# CPU.net
KiCad netlist of a schematic drawn in Altium Designer
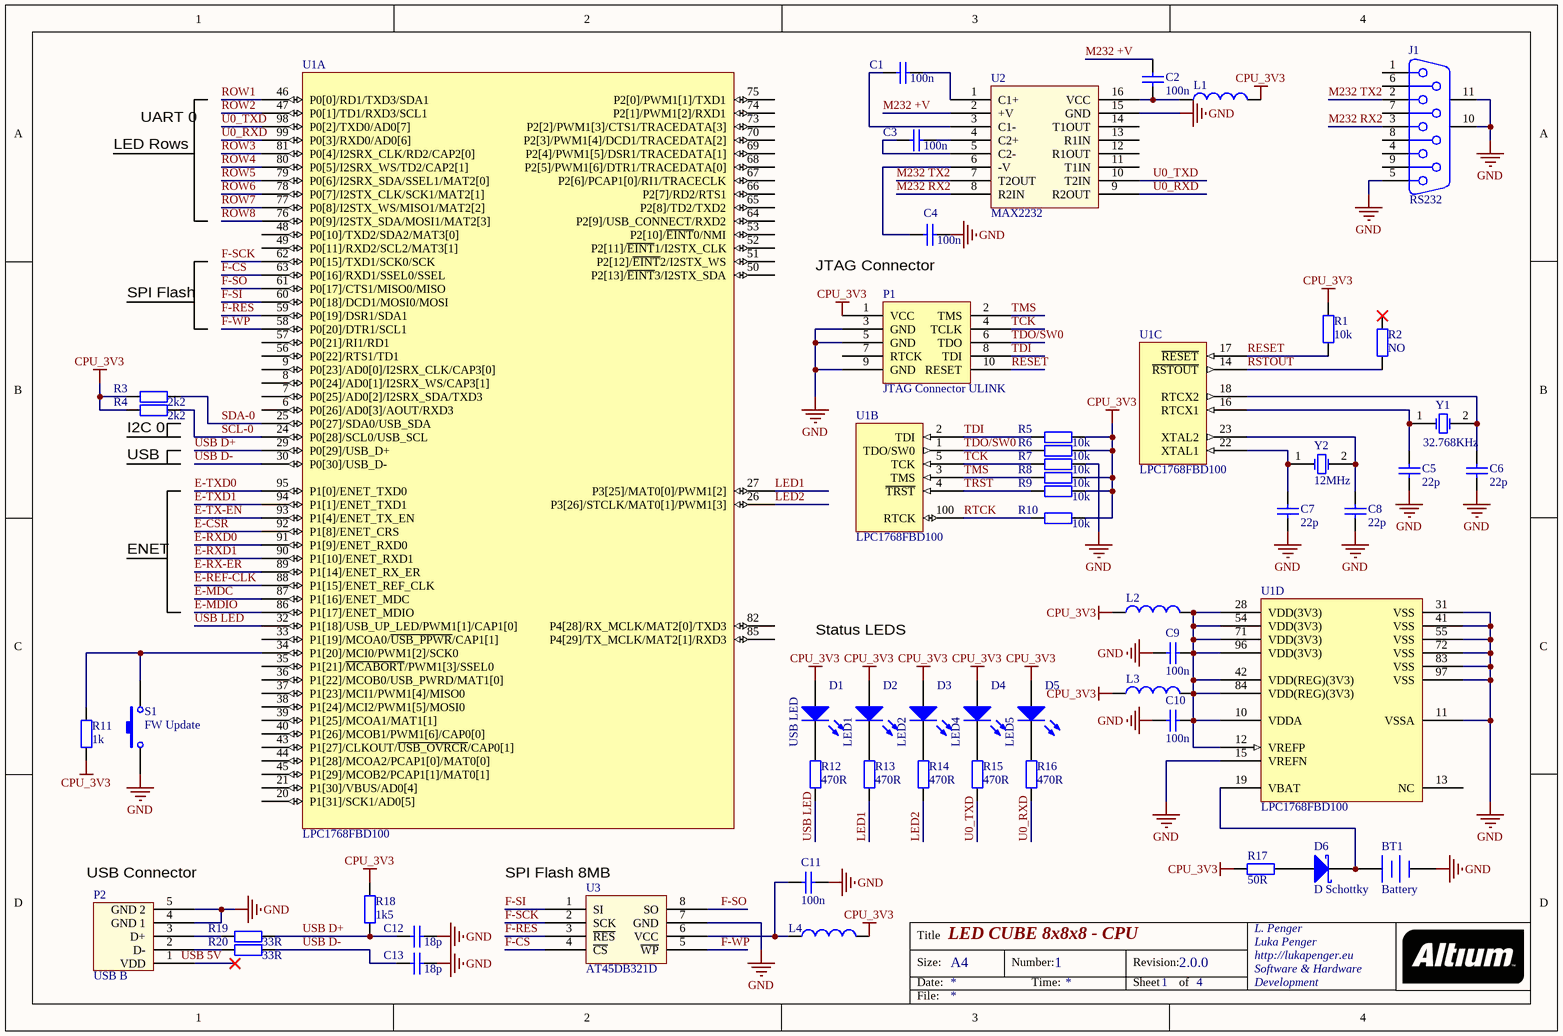
[diagram p0: CPU.SchDoc]

(export (version "E")
  (design (tool "Eeschema 10.0.6"))
  (components
    (comp (ref "BT1")
      (value "Battery")
      (footprint "Battery capacitor")
      (description "Multicell Battery")
      (fields (field (name "PUBLISHER") "Altium Limited"))
      (libsource (lib "Miscellaneous Devices") (part "Battery"))
    )
    (comp (ref "C1")
      (value "100n")
      (footprint "1608[0603]")
      (description "Capacitor")
      (fields (field (name "PUBLISHER") "Altium Limited"))
      (libsource (lib "Miscellaneous Devices") (part "Cap"))
    )
    (comp (ref "C2")
      (value "100n")
      (footprint "1608[0603]")
      (description "Capacitor")
      (fields (field (name "PUBLISHER") "Altium Limited"))
      (libsource (lib "Miscellaneous Devices") (part "Cap"))
    )
    (comp (ref "C3")
      (value "100n")
      (footprint "1608[0603]")
      (description "Capacitor")
      (fields (field (name "PUBLISHER") "Altium Limited"))
      (libsource (lib "Miscellaneous Devices") (part "Cap"))
    )
    (comp (ref "C4")
      (value "100n")
      (footprint "1608[0603]")
      (description "Capacitor")
      (fields (field (name "PUBLISHER") "Altium Limited"))
      (libsource (lib "Miscellaneous Devices") (part "Cap"))
    )
    (comp (ref "C5")
      (value "22p")
      (footprint "1608[0603]")
      (description "Capacitor")
      (fields (field (name "PUBLISHER") "Altium Limited"))
      (libsource (lib "Miscellaneous Devices") (part "Cap"))
    )
    (comp (ref "C6")
      (value "22p")
      (footprint "1608[0603]")
      (description "Capacitor")
      (fields (field (name "PUBLISHER") "Altium Limited"))
      (libsource (lib "Miscellaneous Devices") (part "Cap"))
    )
    (comp (ref "C7")
      (value "22p")
      (footprint "1608[0603]")
      (description "Capacitor")
      (fields (field (name "PUBLISHER") "Altium Limited"))
      (libsource (lib "Miscellaneous Devices") (part "Cap"))
    )
    (comp (ref "C8")
      (value "22p")
      (footprint "1608[0603]")
      (description "Capacitor")
      (fields (field (name "PUBLISHER") "Altium Limited"))
      (libsource (lib "Miscellaneous Devices") (part "Cap"))
    )
    (comp (ref "C9")
      (value "100n")
      (footprint "1608[0603]")
      (description "Capacitor")
      (fields (field (name "PUBLISHER") "Altium Limited"))
      (libsource (lib "Miscellaneous Devices") (part "Cap"))
    )
    (comp (ref "C10")
      (value "100n")
      (footprint "1608[0603]")
      (description "Capacitor")
      (fields (field (name "PUBLISHER") "Altium Limited"))
      (libsource (lib "Miscellaneous Devices") (part "Cap"))
    )
    (comp (ref "C11")
      (value "100n")
      (footprint "1608[0603]")
      (description "Capacitor")
      (fields (field (name "PUBLISHER") "Altium Limited"))
      (libsource (lib "Miscellaneous Devices") (part "Cap"))
    )
    (comp (ref "C12")
      (value "18p")
      (footprint "1608[0603]")
      (description "Capacitor")
      (fields (field (name "PUBLISHER") "Altium Limited"))
      (libsource (lib "Miscellaneous Devices") (part "Cap"))
    )
    (comp (ref "C13")
      (value "18p")
      (footprint "1608[0603]")
      (description "Capacitor")
      (fields (field (name "PUBLISHER") "Altium Limited"))
      (libsource (lib "Miscellaneous Devices") (part "Cap"))
    )
    (comp (ref "D1")
      (value "USB LED")
      (footprint "LED-1")
      (description "Typical INFRARED GaAs LED")
      (fields (field (name "PUBLISHER") "Altium Limited"))
      (libsource (lib "Miscellaneous Devices") (part "LED0"))
    )
    (comp (ref "D2")
      (value "LED1")
      (footprint "LED-1")
      (description "Typical INFRARED GaAs LED")
      (fields (field (name "PUBLISHER") "Altium Limited"))
      (libsource (lib "Miscellaneous Devices") (part "LED0"))
    )
    (comp (ref "D3")
      (value "LED2")
      (footprint "LED-1")
      (description "Typical INFRARED GaAs LED")
      (fields (field (name "PUBLISHER") "Altium Limited"))
      (libsource (lib "Miscellaneous Devices") (part "LED0"))
    )
    (comp (ref "D4")
      (value "LED4")
      (footprint "LED-1")
      (description "Typical INFRARED GaAs LED")
      (fields (field (name "PUBLISHER") "Altium Limited"))
      (libsource (lib "Miscellaneous Devices") (part "LED0"))
    )
    (comp (ref "D5")
      (value "LED5")
      (footprint "LED-1")
      (description "Typical INFRARED GaAs LED")
      (fields (field (name "PUBLISHER") "Altium Limited"))
      (libsource (lib "Miscellaneous Devices") (part "LED0"))
    )
    (comp (ref "D6")
      (value "D Schottky")
      (footprint "SMB")
      (description "Schottky Diode")
      (fields (field (name "PUBLISHER") "Altium Limited"))
      (libsource (lib "Miscellaneous Devices") (part "D Schottky"))
    )
    (comp (ref "J1")
      (value "RS232")
      (footprint "DSUB1.385-2H9")
      (description "Receptacle Assembly, 9 Position, Right Angle")
      (fields (field (name "PUBLISHER") "Altium Limited"))
      (libsource (lib "Miscellaneous Connectors") (part "D Connector 9"))
    )
    (comp (ref "L1")
      (value "Inductor")
      (footprint "1608[0603]")
      (fields (field (name "PUBLISHER") "Altium Limited"))
      (libsource (lib "Miscellaneous Devices") (part "Inductor"))
    )
    (comp (ref "L2")
      (value "Inductor")
      (footprint "1608[0603]")
      (fields (field (name "PUBLISHER") "Altium Limited"))
      (libsource (lib "Miscellaneous Devices") (part "Inductor"))
    )
    (comp (ref "L3")
      (value "Inductor")
      (footprint "1608[0603]")
      (fields (field (name "PUBLISHER") "Altium Limited"))
      (libsource (lib "Miscellaneous Devices") (part "Inductor"))
    )
    (comp (ref "L4")
      (value "Inductor")
      (footprint "1608[0603]")
      (fields (field (name "PUBLISHER") "Altium Limited"))
      (libsource (lib "Miscellaneous Devices") (part "Inductor"))
    )
    (comp (ref "P1")
      (value "JTAG Connector ULINK")
      (footprint "JTAG Connector ULINK")
      (description "JTAG Connector")
      (libsource (lib "LP_Lib") (part "JTAG Connector ULINK"))
    )
    (comp (ref "P2")
      (value "USB B")
      (footprint "USB B")
      (description "USB Connector")
      (libsource (lib "LP_Lib") (part "USB B"))
    )
    (comp (ref "R1")
      (value "10k")
      (footprint "1608[0603]")
      (description "Resistor")
      (fields (field (name "PUBLISHER") "Altium Limited"))
      (libsource (lib "") (part "Res2_1"))
    )
    (comp (ref "R2")
      (value "NO")
      (footprint "1608[0603]")
      (description "Resistor")
      (fields (field (name "PUBLISHER") "Altium Limited"))
      (libsource (lib "") (part "Res2_1"))
    )
    (comp (ref "R3")
      (value "2k2")
      (footprint "1608[0603]")
      (description "Resistor")
      (fields (field (name "PUBLISHER") "Altium Limited"))
      (libsource (lib "") (part "Res2_2"))
    )
    (comp (ref "R4")
      (value "2k2")
      (footprint "1608[0603]")
      (description "Resistor")
      (fields (field (name "PUBLISHER") "Altium Limited"))
      (libsource (lib "") (part "Res2_2"))
    )
    (comp (ref "R5")
      (value "10k")
      (footprint "1608[0603]")
      (description "Resistor")
      (fields (field (name "PUBLISHER") "Altium Limited"))
      (libsource (lib "") (part "Res2_2"))
    )
    (comp (ref "R6")
      (value "10k")
      (footprint "1608[0603]")
      (description "Resistor")
      (fields (field (name "PUBLISHER") "Altium Limited"))
      (libsource (lib "") (part "Res2_2"))
    )
    (comp (ref "R7")
      (value "10k")
      (footprint "1608[0603]")
      (description "Resistor")
      (fields (field (name "PUBLISHER") "Altium Limited"))
      (libsource (lib "") (part "Res2_2"))
    )
    (comp (ref "R8")
      (value "10k")
      (footprint "1608[0603]")
      (description "Resistor")
      (fields (field (name "PUBLISHER") "Altium Limited"))
      (libsource (lib "") (part "Res2_2"))
    )
    (comp (ref "R9")
      (value "10k")
      (footprint "1608[0603]")
      (description "Resistor")
      (fields (field (name "PUBLISHER") "Altium Limited"))
      (libsource (lib "") (part "Res2_2"))
    )
    (comp (ref "R10")
      (value "10k")
      (footprint "1608[0603]")
      (description "Resistor")
      (fields (field (name "PUBLISHER") "Altium Limited"))
      (libsource (lib "") (part "Res2_2"))
    )
    (comp (ref "R11")
      (value "1k")
      (footprint "1608[0603]")
      (description "Resistor")
      (fields (field (name "PUBLISHER") "Altium Limited"))
      (libsource (lib "") (part "Res2_1"))
    )
    (comp (ref "R12")
      (value "470R")
      (footprint "1608[0603]")
      (description "Resistor")
      (fields (field (name "PUBLISHER") "Altium Limited"))
      (libsource (lib "") (part "Res2_1"))
    )
    (comp (ref "R13")
      (value "470R")
      (footprint "1608[0603]")
      (description "Resistor")
      (fields (field (name "PUBLISHER") "Altium Limited"))
      (libsource (lib "") (part "Res2_1"))
    )
    (comp (ref "R14")
      (value "470R")
      (footprint "1608[0603]")
      (description "Resistor")
      (fields (field (name "PUBLISHER") "Altium Limited"))
      (libsource (lib "") (part "Res2_1"))
    )
    (comp (ref "R15")
      (value "470R")
      (footprint "1608[0603]")
      (description "Resistor")
      (fields (field (name "PUBLISHER") "Altium Limited"))
      (libsource (lib "") (part "Res2_1"))
    )
    (comp (ref "R16")
      (value "470R")
      (footprint "1608[0603]")
      (description "Resistor")
      (fields (field (name "PUBLISHER") "Altium Limited"))
      (libsource (lib "") (part "Res2_1"))
    )
    (comp (ref "R17")
      (value "50R")
      (footprint "6-0805_N")
      (description "Resistor")
      (fields (field (name "PUBLISHER") "Altium Limited"))
      (libsource (lib "") (part "Res2_3"))
    )
    (comp (ref "R18")
      (value "1k5")
      (footprint "1608[0603]")
      (description "Resistor")
      (fields (field (name "PUBLISHER") "Altium Limited"))
      (libsource (lib "Miscellaneous Devices") (part "Res2"))
    )
    (comp (ref "R19")
      (value "33R")
      (footprint "1608[0603]")
      (description "Resistor")
      (fields (field (name "PUBLISHER") "Altium Limited"))
      (libsource (lib "") (part "Res2_3"))
    )
    (comp (ref "R20")
      (value "33R")
      (footprint "1608[0603]")
      (description "Resistor")
      (fields (field (name "PUBLISHER") "Altium Limited"))
      (libsource (lib "") (part "Res2_3"))
    )
    (comp (ref "S1")
      (value "FW Update")
      (footprint "SWITCH-TACTILE-90")
      (description "Switch")
      (fields (field (name "PUBLISHER") "Altium Limited"))
      (libsource (lib "Miscellaneous Devices") (part "SW-PB"))
    )
    (comp (ref "U1")
      (value "LPC1768FBD100")
      (footprint "SOT407-1_N")
      (fields (field (name "PUBLISHER") "Altium Limited"))
      (libsource (lib "LukaLIBRARY") (part "LPC1768FBD100"))
    )
    (comp (ref "U2")
      (value "MAX2232")
      (footprint "SOIC16_N")
      (description "Dual 232 +3V3")
      (libsource (lib "LP_Lib") (part "MAX2232"))
    )
    (comp (ref "U3")
      (value "AT45DB321D")
      (footprint "AT45DB321D")
      (description "SPI Flash 32MB")
      (libsource (lib "LP_Lib") (part "AT45DB321D"))
    )
    (comp (ref "Y1")
      (value "32.768KHz")
      (footprint "Crystal 4.1x1.5")
      (description "Crystal Oscillator")
      (fields (field (name "PUBLISHER") "Altium Limited"))
      (libsource (lib "Miscellaneous Devices") (part "XTAL"))
    )
    (comp (ref "Y2")
      (value "12MHz")
      (footprint "5x3.2 Crystal")
      (description "Crystal Oscillator")
      (fields (field (name "PUBLISHER") "Altium Limited"))
      (libsource (lib "Miscellaneous Devices") (part "XTAL"))
    )
  )
  (nets
    (net (code "1") (name "/E-CSR") (class "Default")
      (node (ref "U1") (pin "92") (pinfunction "P1[8]/ENET_CRS_92") (pintype "bidirectional"))
    )
    (net (code "2") (name "/E-MDC") (class "Default")
      (node (ref "U1") (pin "87") (pinfunction "P1[16]/ENET_MDC_87") (pintype "bidirectional"))
    )
    (net (code "3") (name "/E-MDIO") (class "Default")
      (node (ref "U1") (pin "86") (pinfunction "P1[17]/ENET_MDIO_86") (pintype "bidirectional"))
    )
    (net (code "4") (name "/E-REF-CLK") (class "Default")
      (node (ref "U1") (pin "88") (pinfunction "P1[15]/ENET_REF_CLK_88") (pintype "bidirectional"))
    )
    (net (code "5") (name "/E-RX-ER") (class "Default")
      (node (ref "U1") (pin "89") (pinfunction "P1[14]/ENET_RX_ER_89") (pintype "bidirectional"))
    )
    (net (code "6") (name "/E-RXD0") (class "Default")
      (node (ref "U1") (pin "91") (pinfunction "P1[9]/ENET_RXD0_91") (pintype "bidirectional"))
    )
    (net (code "7") (name "/E-RXD1") (class "Default")
      (node (ref "U1") (pin "90") (pinfunction "P1[10]/ENET_RXD1_90") (pintype "bidirectional"))
    )
    (net (code "8") (name "/E-TX-EN") (class "Default")
      (node (ref "U1") (pin "93") (pinfunction "P1[4]/ENET_TX_EN_93") (pintype "bidirectional"))
    )
    (net (code "9") (name "/E-TXD0") (class "Default")
      (node (ref "U1") (pin "95") (pinfunction "P1[0]/ENET_TXD0_95") (pintype "bidirectional"))
    )
    (net (code "10") (name "/E-TXD1") (class "Default")
      (node (ref "U1") (pin "94") (pinfunction "P1[1]/ENET_TXD1_94") (pintype "bidirectional"))
    )
    (net (code "11") (name "/F-CS") (class "Default")
      (node (ref "U1") (pin "63") (pinfunction "P0[16]/RXD1/SSEL0/SSEL_63") (pintype "bidirectional"))
      (node (ref "U3") (pin "4") (pinfunction "~{CS}_4") (pintype "passive"))
    )
    (net (code "12") (name "/F-RES") (class "Default")
      (node (ref "U1") (pin "59") (pinfunction "P0[19]/DSR1/SDA1_59") (pintype "bidirectional"))
      (node (ref "U3") (pin "3") (pinfunction "~{RES}_3") (pintype "passive"))
    )
    (net (code "13") (name "/F-SCK") (class "Default")
      (node (ref "U1") (pin "62") (pinfunction "P0[15]/TXD1/SCK0/SCK_62") (pintype "bidirectional"))
      (node (ref "U3") (pin "2") (pinfunction "SCK_2") (pintype "passive"))
    )
    (net (code "14") (name "/F-SI") (class "Default")
      (node (ref "U1") (pin "60") (pinfunction "P0[18]/DCD1/MOSI0/MOSI_60") (pintype "bidirectional"))
      (node (ref "U3") (pin "1") (pinfunction "SI_1") (pintype "passive"))
    )
    (net (code "15") (name "/F-SO") (class "Default")
      (node (ref "U1") (pin "61") (pinfunction "P0[17]/CTS1/MISO0/MISO_61") (pintype "bidirectional"))
      (node (ref "U3") (pin "8") (pinfunction "SO_8") (pintype "passive"))
    )
    (net (code "16") (name "/F-WP") (class "Default")
      (node (ref "U1") (pin "58") (pinfunction "P0[20]/DTR1/SCL1_58") (pintype "bidirectional"))
      (node (ref "U3") (pin "5") (pinfunction "~{WP}_5") (pintype "passive"))
    )
    (net (code "17") (name "/LED1") (class "Default")
      (node (ref "R13") (pin "1") (pinfunction "1_1") (pintype "passive"))
      (node (ref "U1") (pin "27") (pinfunction "P3[25]/MAT0[0]/PWM1[2]_27") (pintype "bidirectional"))
    )
    (net (code "18") (name "/LED2") (class "Default")
      (node (ref "R14") (pin "1") (pinfunction "1_1") (pintype "passive"))
      (node (ref "U1") (pin "26") (pinfunction "P3[26]/STCLK/MAT0[1]/PWM1[3]_26") (pintype "bidirectional"))
    )
    (net (code "19") (name "/M232 +V") (class "Default")
      (node (ref "C2") (pin "1") (pinfunction "1_1") (pintype "passive"))
      (node (ref "U2") (pin "2") (pinfunction "+V_2") (pintype "passive"))
    )
    (net (code "20") (name "/M232 RX2") (class "Default")
      (node (ref "J1") (pin "3") (pinfunction "3_3") (pintype "passive"))
      (node (ref "U2") (pin "8") (pinfunction "R2IN_8") (pintype "passive"))
    )
    (net (code "21") (name "/M232 TX2") (class "Default")
      (node (ref "J1") (pin "2") (pinfunction "2_2") (pintype "passive"))
      (node (ref "U2") (pin "7") (pinfunction "T2OUT_7") (pintype "passive"))
    )
    (net (code "22") (name "/RESET") (class "Default")
      (node (ref "P1") (pin "10") (pinfunction "RESET_10") (pintype "passive"))
      (node (ref "R1") (pin "1") (pinfunction "1_1") (pintype "passive"))
      (node (ref "U1") (pin "17") (pinfunction "~{RESET}_17") (pintype "input"))
    )
    (net (code "23") (name "/ROW1") (class "Default")
      (node (ref "U1") (pin "46") (pinfunction "P0[0]/RD1/TXD3/SDA1_46") (pintype "bidirectional"))
    )
    (net (code "24") (name "/ROW2") (class "Default")
      (node (ref "U1") (pin "47") (pinfunction "P0[1]/TD1/RXD3/SCL1_47") (pintype "bidirectional"))
    )
    (net (code "25") (name "/ROW3") (class "Default")
      (node (ref "U1") (pin "81") (pinfunction "P0[4]/I2SRX_CLK/RD2/CAP2[0]_81") (pintype "bidirectional"))
    )
    (net (code "26") (name "/ROW4") (class "Default")
      (node (ref "U1") (pin "80") (pinfunction "P0[5]/I2SRX_WS/TD2/CAP2[1]_80") (pintype "bidirectional"))
    )
    (net (code "27") (name "/ROW5") (class "Default")
      (node (ref "U1") (pin "79") (pinfunction "P0[6]/I2SRX_SDA/SSEL1/MAT2[0]_79") (pintype "bidirectional"))
    )
    (net (code "28") (name "/ROW6") (class "Default")
      (node (ref "U1") (pin "78") (pinfunction "P0[7]/I2STX_CLK/SCK1/MAT2[1]_78") (pintype "bidirectional"))
    )
    (net (code "29") (name "/ROW7") (class "Default")
      (node (ref "U1") (pin "77") (pinfunction "P0[8]/I2STX_WS/MISO1/MAT2[2]_77") (pintype "bidirectional"))
    )
    (net (code "30") (name "/ROW8") (class "Default")
      (node (ref "U1") (pin "76") (pinfunction "P0[9]/I2STX_SDA/MOSI1/MAT2[3]_76") (pintype "bidirectional"))
    )
    (net (code "31") (name "/RSTOUT") (class "Default")
      (node (ref "R2") (pin "1") (pinfunction "1_1") (pintype "passive"))
      (node (ref "U1") (pin "14") (pinfunction "~{RSTOUT}_14") (pintype "output"))
    )
    (net (code "32") (name "/RTCK") (class "Default")
      (node (ref "R10") (pin "1") (pinfunction "1_1") (pintype "passive"))
      (node (ref "U1") (pin "100") (pinfunction "RTCK_100") (pintype "bidirectional"))
    )
    (net (code "33") (name "/SCL-0") (class "Default")
      (node (ref "R4") (pin "2") (pinfunction "2_2") (pintype "passive"))
      (node (ref "U1") (pin "24") (pinfunction "P0[28]/SCL0/USB_SCL_24") (pintype "bidirectional"))
    )
    (net (code "34") (name "/SDA-0") (class "Default")
      (node (ref "R3") (pin "2") (pinfunction "2_2") (pintype "passive"))
      (node (ref "U1") (pin "25") (pinfunction "P0[27]/SDA0/USB_SDA_25") (pintype "bidirectional"))
    )
    (net (code "35") (name "/TCK") (class "Default")
      (node (ref "P1") (pin "4") (pinfunction "TCLK_4") (pintype "passive"))
      (node (ref "R7") (pin "1") (pinfunction "1_1") (pintype "passive"))
      (node (ref "U1") (pin "5") (pinfunction "TCK_5") (pintype "input"))
    )
    (net (code "36") (name "/TDI") (class "Default")
      (node (ref "P1") (pin "8") (pinfunction "TDI_8") (pintype "passive"))
      (node (ref "R5") (pin "1") (pinfunction "1_1") (pintype "passive"))
      (node (ref "U1") (pin "2") (pinfunction "TDI_2") (pintype "input"))
    )
    (net (code "37") (name "/TDO{slash}SW0") (class "Default")
      (node (ref "P1") (pin "6") (pinfunction "TDO_6") (pintype "passive"))
      (node (ref "R6") (pin "1") (pinfunction "1_1") (pintype "passive"))
      (node (ref "U1") (pin "1") (pinfunction "TDO/SW0_1") (pintype "output"))
    )
    (net (code "38") (name "/TMS") (class "Default")
      (node (ref "P1") (pin "2") (pinfunction "TMS_2") (pintype "passive"))
      (node (ref "R8") (pin "1") (pinfunction "1_1") (pintype "passive"))
      (node (ref "U1") (pin "3") (pinfunction "TMS_3") (pintype "input"))
    )
    (net (code "39") (name "/TRST") (class "Default")
      (node (ref "R9") (pin "1") (pinfunction "1_1") (pintype "passive"))
      (node (ref "U1") (pin "4") (pinfunction "~{TRST}_4") (pintype "input"))
    )
    (net (code "40") (name "/U0_RXD") (class "Default")
      (node (ref "R16") (pin "1") (pinfunction "1_1") (pintype "passive"))
      (node (ref "U1") (pin "99") (pinfunction "P0[3]/RXD0/AD0[6]_99") (pintype "bidirectional"))
      (node (ref "U2") (pin "9") (pinfunction "R2OUT_9") (pintype "passive"))
    )
    (net (code "41") (name "/U0_TXD") (class "Default")
      (node (ref "R15") (pin "1") (pinfunction "1_1") (pintype "passive"))
      (node (ref "U1") (pin "98") (pinfunction "P0[2]/TXD0/AD0[7]_98") (pintype "bidirectional"))
      (node (ref "U2") (pin "10") (pinfunction "T2IN_10") (pintype "passive"))
    )
    (net (code "43") (name "/USB D+") (class "Default")
      (node (ref "C12") (pin "1") (pinfunction "1_1") (pintype "passive"))
      (node (ref "R18") (pin "2") (pinfunction "2_2") (pintype "passive"))
      (node (ref "R19") (pin "1") (pinfunction "1_1") (pintype "passive"))
      (node (ref "U1") (pin "29") (pinfunction "P0[29]/USB_D+_29") (pintype "bidirectional"))
    )
    (net (code "44") (name "/USB D-") (class "Default")
      (node (ref "C13") (pin "1") (pinfunction "1_1") (pintype "passive"))
      (node (ref "R20") (pin "1") (pinfunction "1_1") (pintype "passive"))
      (node (ref "U1") (pin "30") (pinfunction "P0[30]/USB_D-_30") (pintype "bidirectional"))
    )
    (net (code "45") (name "/USB LED") (class "Default")
      (node (ref "R12") (pin "1") (pinfunction "1_1") (pintype "passive"))
      (node (ref "U1") (pin "32") (pinfunction "P1[18]/USB_UP_LED/PWM1[1]/CAP1[0]_32") (pintype "bidirectional"))
    )
    (net (code "46") (name "CPU_3V3") (class "Default")
      (node (ref "D1") (pin "1") (pinfunction "A_1") (pintype "passive"))
      (node (ref "D2") (pin "1") (pinfunction "A_1") (pintype "passive"))
      (node (ref "D3") (pin "1") (pinfunction "A_1") (pintype "passive"))
      (node (ref "D4") (pin "1") (pinfunction "A_1") (pintype "passive"))
      (node (ref "D5") (pin "1") (pinfunction "A_1") (pintype "passive"))
      (node (ref "L1") (pin "2") (pinfunction "2_2") (pintype "passive"))
      (node (ref "L2") (pin "1") (pinfunction "1_1") (pintype "passive"))
      (node (ref "L3") (pin "1") (pinfunction "1_1") (pintype "passive"))
      (node (ref "L4") (pin "2") (pinfunction "2_2") (pintype "passive"))
      (node (ref "P1") (pin "1") (pinfunction "VCC_1") (pintype "passive"))
      (node (ref "R1") (pin "2") (pinfunction "2_2") (pintype "passive"))
      (node (ref "R10") (pin "2") (pinfunction "2_2") (pintype "passive"))
      (node (ref "R11") (pin "1") (pinfunction "1_1") (pintype "passive"))
      (node (ref "R17") (pin "2") (pinfunction "2_2") (pintype "passive"))
      (node (ref "R18") (pin "1") (pinfunction "1_1") (pintype "passive"))
      (node (ref "R3") (pin "1") (pinfunction "1_1") (pintype "passive"))
      (node (ref "R4") (pin "1") (pinfunction "1_1") (pintype "passive"))
      (node (ref "R5") (pin "2") (pinfunction "2_2") (pintype "passive"))
      (node (ref "R6") (pin "2") (pinfunction "2_2") (pintype "passive"))
      (node (ref "R8") (pin "2") (pinfunction "2_2") (pintype "passive"))
      (node (ref "R9") (pin "2") (pinfunction "2_2") (pintype "passive"))
    )
    (net (code "47") (name "GND") (class "Default")
      (node (ref "BT1") (pin "2") (pinfunction "-_2") (pintype "passive"))
      (node (ref "C10") (pin "1") (pinfunction "1_1") (pintype "passive"))
      (node (ref "C11") (pin "1") (pinfunction "1_1") (pintype "passive"))
      (node (ref "C12") (pin "2") (pinfunction "2_2") (pintype "passive"))
      (node (ref "C13") (pin "2") (pinfunction "2_2") (pintype "passive"))
      (node (ref "C4") (pin "1") (pinfunction "1_1") (pintype "passive"))
      (node (ref "C5") (pin "1") (pinfunction "1_1") (pintype "passive"))
      (node (ref "C6") (pin "1") (pinfunction "1_1") (pintype "passive"))
      (node (ref "C7") (pin "1") (pinfunction "1_1") (pintype "passive"))
      (node (ref "C8") (pin "1") (pinfunction "1_1") (pintype "passive"))
      (node (ref "C9") (pin "2") (pinfunction "2_2") (pintype "passive"))
      (node (ref "J1") (pin "10") (pinfunction "MH1_10") (pintype "passive"))
      (node (ref "J1") (pin "11") (pinfunction "MH2_11") (pintype "passive"))
      (node (ref "J1") (pin "5") (pinfunction "5_5") (pintype "passive"))
      (node (ref "P1") (pin "3") (pinfunction "GND_3") (pintype "passive"))
      (node (ref "P1") (pin "5") (pinfunction "GND_5") (pintype "passive"))
      (node (ref "P1") (pin "9") (pinfunction "GND_9") (pintype "passive"))
      (node (ref "P2") (pin "4") (pinfunction "GND_1_4") (pintype "passive"))
      (node (ref "P2") (pin "5") (pinfunction "GND_2_5") (pintype "passive"))
      (node (ref "R7") (pin "2") (pinfunction "2_2") (pintype "passive"))
      (node (ref "S1") (pin "1") (pinfunction "1_1") (pintype "passive"))
      (node (ref "U1") (pin "11") (pinfunction "VSSA_11") (pintype "power_in"))
      (node (ref "U1") (pin "15") (pinfunction "VREFN_15") (pintype "power_in"))
      (node (ref "U1") (pin "31") (pinfunction "VSS_31") (pintype "power_in"))
      (node (ref "U1") (pin "41") (pinfunction "VSS_41") (pintype "power_in"))
      (node (ref "U1") (pin "55") (pinfunction "VSS_55") (pintype "power_in"))
      (node (ref "U1") (pin "72") (pinfunction "VSS_72") (pintype "power_in"))
      (node (ref "U1") (pin "83") (pinfunction "VSS_83") (pintype "power_in"))
      (node (ref "U1") (pin "97") (pinfunction "VSS_97") (pintype "power_in"))
      (node (ref "U2") (pin "15") (pinfunction "GND_15") (pintype "passive"))
      (node (ref "U3") (pin "7") (pinfunction "GND_7") (pintype "passive"))
    )
    (net (code "48") (name "Net-(BT1-+)") (class "Default")
      (node (ref "BT1") (pin "1") (pinfunction "+_1") (pintype "passive"))
      (node (ref "D6") (pin "2") (pinfunction "K_2") (pintype "passive"))
      (node (ref "U1") (pin "19") (pinfunction "VBAT_19") (pintype "power_in"))
    )
    (net (code "49") (name "Net-(D1-K)") (class "Default")
      (node (ref "D1") (pin "2") (pinfunction "K_2") (pintype "passive"))
      (node (ref "R12") (pin "2") (pinfunction "2_2") (pintype "passive"))
    )
    (net (code "50") (name "Net-(D2-K)") (class "Default")
      (node (ref "D2") (pin "2") (pinfunction "K_2") (pintype "passive"))
      (node (ref "R13") (pin "2") (pinfunction "2_2") (pintype "passive"))
    )
    (net (code "51") (name "Net-(D3-K)") (class "Default")
      (node (ref "D3") (pin "2") (pinfunction "K_2") (pintype "passive"))
      (node (ref "R14") (pin "2") (pinfunction "2_2") (pintype "passive"))
    )
    (net (code "52") (name "Net-(D4-K)") (class "Default")
      (node (ref "D4") (pin "2") (pinfunction "K_2") (pintype "passive"))
      (node (ref "R15") (pin "2") (pinfunction "2_2") (pintype "passive"))
    )
    (net (code "53") (name "Net-(D5-K)") (class "Default")
      (node (ref "D5") (pin "2") (pinfunction "K_2") (pintype "passive"))
      (node (ref "R16") (pin "2") (pinfunction "2_2") (pintype "passive"))
    )
    (net (code "54") (name "Net-(D6-A)") (class "Default")
      (node (ref "D6") (pin "1") (pinfunction "A_1") (pintype "passive"))
      (node (ref "R17") (pin "1") (pinfunction "1_1") (pintype "passive"))
    )
    (net (code "55") (name "Net-(P2-D+)") (class "Default")
      (node (ref "P2") (pin "3") (pinfunction "D+_3") (pintype "passive"))
      (node (ref "R19") (pin "2") (pinfunction "2_2") (pintype "passive"))
    )
    (net (code "56") (name "Net-(P2-D-)") (class "Default")
      (node (ref "P2") (pin "2") (pinfunction "D-_2") (pintype "passive"))
      (node (ref "R20") (pin "2") (pinfunction "2_2") (pintype "passive"))
    )
    (net (code "57") (name "Net-(U1A-P1[20]{slash}MCI0{slash}PWM1[2]{slash}SCK0)") (class "Default")
      (node (ref "R11") (pin "2") (pinfunction "2_2") (pintype "passive"))
      (node (ref "S1") (pin "2") (pinfunction "2_2") (pintype "passive"))
      (node (ref "U1") (pin "34") (pinfunction "P1[20]/MCI0/PWM1[2]/SCK0_34") (pintype "bidirectional"))
    )
    (net (code "58") (name "Net-(U1C-RTCX1)") (class "Default")
      (node (ref "C5") (pin "2") (pinfunction "2_2") (pintype "passive"))
      (node (ref "U1") (pin "16") (pinfunction "RTCX1_16") (pintype "input"))
      (node (ref "Y1") (pin "1") (pinfunction "OSC1_1") (pintype "passive"))
    )
    (net (code "59") (name "Net-(U1C-RTCX2)") (class "Default")
      (node (ref "C6") (pin "2") (pinfunction "2_2") (pintype "passive"))
      (node (ref "U1") (pin "18") (pinfunction "RTCX2_18") (pintype "output"))
      (node (ref "Y1") (pin "2") (pinfunction "OSC2_2") (pintype "passive"))
    )
    (net (code "60") (name "Net-(U1C-XTAL1)") (class "Default")
      (node (ref "C7") (pin "2") (pinfunction "2_2") (pintype "passive"))
      (node (ref "U1") (pin "22") (pinfunction "XTAL1_22") (pintype "input"))
      (node (ref "Y2") (pin "1") (pinfunction "OSC1_1") (pintype "passive"))
    )
    (net (code "61") (name "Net-(U1C-XTAL2)") (class "Default")
      (node (ref "C8") (pin "2") (pinfunction "2_2") (pintype "passive"))
      (node (ref "U1") (pin "23") (pinfunction "XTAL2_23") (pintype "output"))
      (node (ref "Y2") (pin "2") (pinfunction "OSC2_2") (pintype "passive"))
    )
    (net (code "62") (name "Net-(U1D-VDDA)") (class "Default")
      (node (ref "C10") (pin "2") (pinfunction "2_2") (pintype "passive"))
      (node (ref "C9") (pin "1") (pinfunction "1_1") (pintype "passive"))
      (node (ref "L2") (pin "2") (pinfunction "2_2") (pintype "passive"))
      (node (ref "L3") (pin "2") (pinfunction "2_2") (pintype "passive"))
      (node (ref "U1") (pin "10") (pinfunction "VDDA_10") (pintype "power_in"))
      (node (ref "U1") (pin "12") (pinfunction "VREFP_12") (pintype "input"))
      (node (ref "U1") (pin "28") (pinfunction "VDD(3V3)_28") (pintype "power_in"))
      (node (ref "U1") (pin "42") (pinfunction "VDD(REG)(3V3)_42") (pintype "power_in"))
      (node (ref "U1") (pin "54") (pinfunction "VDD(3V3)_54") (pintype "power_in"))
      (node (ref "U1") (pin "71") (pinfunction "VDD(3V3)_71") (pintype "power_in"))
      (node (ref "U1") (pin "84") (pinfunction "VDD(REG)(3V3)_84") (pintype "power_in"))
      (node (ref "U1") (pin "96") (pinfunction "VDD(3V3)_96") (pintype "power_in"))
    )
    (net (code "63") (name "Net-(U2--V)") (class "Default")
      (node (ref "C4") (pin "2") (pinfunction "2_2") (pintype "passive"))
      (node (ref "U2") (pin "6") (pinfunction "-V_6") (pintype "passive"))
    )
    (net (code "64") (name "Net-(U2-C1+)") (class "Default")
      (node (ref "C1") (pin "2") (pinfunction "2_2") (pintype "passive"))
      (node (ref "U2") (pin "1") (pinfunction "C1+_1") (pintype "passive"))
    )
    (net (code "65") (name "Net-(U2-C1-)") (class "Default")
      (node (ref "C1") (pin "1") (pinfunction "1_1") (pintype "passive"))
      (node (ref "U2") (pin "3") (pinfunction "C1-_3") (pintype "passive"))
    )
    (net (code "66") (name "Net-(U2-C2+)") (class "Default")
      (node (ref "C3") (pin "2") (pinfunction "2_2") (pintype "passive"))
      (node (ref "U2") (pin "4") (pinfunction "C2+_4") (pintype "passive"))
    )
    (net (code "67") (name "Net-(U2-C2-)") (class "Default")
      (node (ref "C3") (pin "1") (pinfunction "1_1") (pintype "passive"))
      (node (ref "U2") (pin "5") (pinfunction "C2-_5") (pintype "passive"))
    )
    (net (code "68") (name "Net-(U2-VCC)") (class "Default")
      (node (ref "C2") (pin "2") (pinfunction "2_2") (pintype "passive"))
      (node (ref "L1") (pin "1") (pinfunction "1_1") (pintype "passive"))
      (node (ref "U2") (pin "16") (pinfunction "VCC_16") (pintype "passive"))
    )
    (net (code "69") (name "Net-(U3-VCC)") (class "Default")
      (node (ref "C11") (pin "2") (pinfunction "2_2") (pintype "passive"))
      (node (ref "L4") (pin "1") (pinfunction "1_1") (pintype "passive"))
      (node (ref "U3") (pin "6") (pinfunction "VCC_6") (pintype "passive"))
    )
    (net (code "70") (name "unconnected-(J1-Pad1)") (class "Default")
      (node (ref "J1") (pin "1") (pinfunction "1_1") (pintype "passive"))
    )
    (net (code "71") (name "unconnected-(J1-Pad4)") (class "Default")
      (node (ref "J1") (pin "4") (pinfunction "4_4") (pintype "passive"))
    )
    (net (code "72") (name "unconnected-(J1-Pad6)") (class "Default")
      (node (ref "J1") (pin "6") (pinfunction "6_6") (pintype "passive"))
    )
    (net (code "73") (name "unconnected-(J1-Pad7)") (class "Default")
      (node (ref "J1") (pin "7") (pinfunction "7_7") (pintype "passive"))
    )
    (net (code "74") (name "unconnected-(J1-Pad8)") (class "Default")
      (node (ref "J1") (pin "8") (pinfunction "8_8") (pintype "passive"))
    )
    (net (code "75") (name "unconnected-(J1-Pad9)") (class "Default")
      (node (ref "J1") (pin "9") (pinfunction "9_9") (pintype "passive"))
    )
    (net (code "76") (name "unconnected-(P1-RTCK-Pad7)") (class "Default")
      (node (ref "P1") (pin "7") (pinfunction "RTCK_7") (pintype "passive"))
    )
    (net (code "77") (name "unconnected-(P2-VDD-Pad1)") (class "Default")
      (node (ref "P2") (pin "1") (pinfunction "VDD_1") (pintype "passive+no_connect"))
    )
    (net (code "78") (name "unconnected-(R2-Pad2)") (class "Default")
      (node (ref "R2") (pin "2") (pinfunction "2_2") (pintype "passive+no_connect"))
    )
    (net (code "79") (name "unconnected-(U1A-P0[10]{slash}TXD2{slash}SDA2{slash}MAT3[0]-Pad48)") (class "Default")
      (node (ref "U1") (pin "48") (pinfunction "P0[10]/TXD2/SDA2/MAT3[0]_48") (pintype "bidirectional"))
    )
    (net (code "80") (name "unconnected-(U1A-P0[11]{slash}RXD2{slash}SCL2{slash}MAT3[1]-Pad49)") (class "Default")
      (node (ref "U1") (pin "49") (pinfunction "P0[11]/RXD2/SCL2/MAT3[1]_49") (pintype "bidirectional"))
    )
    (net (code "81") (name "unconnected-(U1A-P0[21]{slash}RI1{slash}RD1-Pad57)") (class "Default")
      (node (ref "U1") (pin "57") (pinfunction "P0[21]/RI1/RD1_57") (pintype "bidirectional"))
    )
    (net (code "82") (name "unconnected-(U1A-P0[22]{slash}RTS1{slash}TD1-Pad56)") (class "Default")
      (node (ref "U1") (pin "56") (pinfunction "P0[22]/RTS1/TD1_56") (pintype "bidirectional"))
    )
    (net (code "83") (name "unconnected-(U1A-P0[23]{slash}AD0[0]{slash}I2SRX_CLK{slash}CAP3[0]-Pad9)") (class "Default")
      (node (ref "U1") (pin "9") (pinfunction "P0[23]/AD0[0]/I2SRX_CLK/CAP3[0]_9") (pintype "bidirectional"))
    )
    (net (code "84") (name "unconnected-(U1A-P0[24]{slash}AD0[1]{slash}I2SRX_WS{slash}CAP3[1]-Pad8)") (class "Default")
      (node (ref "U1") (pin "8") (pinfunction "P0[24]/AD0[1]/I2SRX_WS/CAP3[1]_8") (pintype "bidirectional"))
    )
    (net (code "85") (name "unconnected-(U1A-P0[25]{slash}AD0[2]{slash}I2SRX_SDA{slash}TXD3-Pad7)") (class "Default")
      (node (ref "U1") (pin "7") (pinfunction "P0[25]/AD0[2]/I2SRX_SDA/TXD3_7") (pintype "bidirectional"))
    )
    (net (code "86") (name "unconnected-(U1A-P0[26]{slash}AD0[3]{slash}AOUT{slash}RXD3-Pad6)") (class "Default")
      (node (ref "U1") (pin "6") (pinfunction "P0[26]/AD0[3]/AOUT/RXD3_6") (pintype "bidirectional"))
    )
    (net (code "87") (name "unconnected-(U1A-P1[19]{slash}MCOA0{slash}~{USB_PPWR}{slash}CAP1[1]-Pad33)") (class "Default")
      (node (ref "U1") (pin "33") (pinfunction "P1[19]/MCOA0/~{USB_PPWR}/CAP1[1]_33") (pintype "bidirectional"))
    )
    (net (code "88") (name "unconnected-(U1A-P1[21]{slash}~{MCABORT}{slash}PWM1[3]{slash}SSEL0-Pad35)") (class "Default")
      (node (ref "U1") (pin "35") (pinfunction "P1[21]/~{MCABORT}/PWM1[3]/SSEL0_35") (pintype "bidirectional"))
    )
    (net (code "89") (name "unconnected-(U1A-P1[22]{slash}MCOB0{slash}USB_PWRD{slash}MAT1[0]-Pad36)") (class "Default")
      (node (ref "U1") (pin "36") (pinfunction "P1[22]/MCOB0/USB_PWRD/MAT1[0]_36") (pintype "bidirectional"))
    )
    (net (code "90") (name "unconnected-(U1A-P1[23]{slash}MCI1{slash}PWM1[4]{slash}MISO0-Pad37)") (class "Default")
      (node (ref "U1") (pin "37") (pinfunction "P1[23]/MCI1/PWM1[4]/MISO0_37") (pintype "bidirectional"))
    )
    (net (code "91") (name "unconnected-(U1A-P1[24]{slash}MCI2{slash}PWM1[5]{slash}MOSI0-Pad38)") (class "Default")
      (node (ref "U1") (pin "38") (pinfunction "P1[24]/MCI2/PWM1[5]/MOSI0_38") (pintype "bidirectional"))
    )
    (net (code "92") (name "unconnected-(U1A-P1[25]{slash}MCOA1{slash}MAT1[1]-Pad39)") (class "Default")
      (node (ref "U1") (pin "39") (pinfunction "P1[25]/MCOA1/MAT1[1]_39") (pintype "bidirectional"))
    )
    (net (code "93") (name "unconnected-(U1A-P1[26]{slash}MCOB1{slash}PWM1[6]{slash}CAP0[0]-Pad40)") (class "Default")
      (node (ref "U1") (pin "40") (pinfunction "P1[26]/MCOB1/PWM1[6]/CAP0[0]_40") (pintype "bidirectional"))
    )
    (net (code "94") (name "unconnected-(U1A-P1[27]{slash}CLKOUT{slash}~{USB_OVRCR}{slash}CAP0[1]-Pad43)") (class "Default")
      (node (ref "U1") (pin "43") (pinfunction "P1[27]/CLKOUT/~{USB_OVRCR}/CAP0[1]_43") (pintype "bidirectional"))
    )
    (net (code "95") (name "unconnected-(U1A-P1[28]{slash}MCOA2{slash}PCAP1[0]{slash}MAT0[0]-Pad44)") (class "Default")
      (node (ref "U1") (pin "44") (pinfunction "P1[28]/MCOA2/PCAP1[0]/MAT0[0]_44") (pintype "bidirectional"))
    )
    (net (code "96") (name "unconnected-(U1A-P1[29]{slash}MCOB2{slash}PCAP1[1]{slash}MAT0[1]-Pad45)") (class "Default")
      (node (ref "U1") (pin "45") (pinfunction "P1[29]/MCOB2/PCAP1[1]/MAT0[1]_45") (pintype "bidirectional"))
    )
    (net (code "97") (name "unconnected-(U1A-P1[30]{slash}VBUS{slash}AD0[4]-Pad21)") (class "Default")
      (node (ref "U1") (pin "21") (pinfunction "P1[30]/VBUS/AD0[4]_21") (pintype "bidirectional"))
    )
    (net (code "98") (name "unconnected-(U1A-P1[31]{slash}SCK1{slash}AD0[5]-Pad20)") (class "Default")
      (node (ref "U1") (pin "20") (pinfunction "P1[31]/SCK1/AD0[5]_20") (pintype "bidirectional"))
    )
    (net (code "99") (name "unconnected-(U1A-P2[0]{slash}PWM1[1]{slash}TXD1-Pad75)") (class "Default")
      (node (ref "U1") (pin "75") (pinfunction "P2[0]/PWM1[1]/TXD1_75") (pintype "bidirectional"))
    )
    (net (code "100") (name "unconnected-(U1A-P2[1]{slash}PWM1[2]{slash}RXD1-Pad74)") (class "Default")
      (node (ref "U1") (pin "74") (pinfunction "P2[1]/PWM1[2]/RXD1_74") (pintype "bidirectional"))
    )
    (net (code "101") (name "unconnected-(U1A-P2[2]{slash}PWM1[3]{slash}CTS1{slash}TRACEDATA[3]-Pad73)") (class "Default")
      (node (ref "U1") (pin "73") (pinfunction "P2[2]/PWM1[3]/CTS1/TRACEDATA[3]_73") (pintype "bidirectional"))
    )
    (net (code "102") (name "unconnected-(U1A-P2[3]{slash}PWM1[4]{slash}DCD1{slash}TRACEDATA[2]-Pad70)") (class "Default")
      (node (ref "U1") (pin "70") (pinfunction "P2[3]/PWM1[4]/DCD1/TRACEDATA[2]_70") (pintype "bidirectional"))
    )
    (net (code "103") (name "unconnected-(U1A-P2[4]{slash}PWM1[5]{slash}DSR1{slash}TRACEDATA[1]-Pad69)") (class "Default")
      (node (ref "U1") (pin "69") (pinfunction "P2[4]/PWM1[5]/DSR1/TRACEDATA[1]_69") (pintype "bidirectional"))
    )
    (net (code "104") (name "unconnected-(U1A-P2[5]{slash}PWM1[6]{slash}DTR1{slash}TRACEDATA[0]-Pad68)") (class "Default")
      (node (ref "U1") (pin "68") (pinfunction "P2[5]/PWM1[6]/DTR1/TRACEDATA[0]_68") (pintype "bidirectional"))
    )
    (net (code "105") (name "unconnected-(U1A-P2[6]{slash}PCAP1[0]{slash}RI1{slash}TRACECLK-Pad67)") (class "Default")
      (node (ref "U1") (pin "67") (pinfunction "P2[6]/PCAP1[0]/RI1/TRACECLK_67") (pintype "bidirectional"))
    )
    (net (code "106") (name "unconnected-(U1A-P2[7]{slash}RD2{slash}RTS1-Pad66)") (class "Default")
      (node (ref "U1") (pin "66") (pinfunction "P2[7]/RD2/RTS1_66") (pintype "bidirectional"))
    )
    (net (code "107") (name "unconnected-(U1A-P2[8]{slash}TD2{slash}TXD2-Pad65)") (class "Default")
      (node (ref "U1") (pin "65") (pinfunction "P2[8]/TD2/TXD2_65") (pintype "bidirectional"))
    )
    (net (code "108") (name "unconnected-(U1A-P2[9]{slash}USB_CONNECT{slash}RXD2-Pad64)") (class "Default")
      (node (ref "U1") (pin "64") (pinfunction "P2[9]/USB_CONNECT/RXD2_64") (pintype "bidirectional"))
    )
    (net (code "109") (name "unconnected-(U1A-P2[10]{slash}~{EINT}0{slash}NMI-Pad53)") (class "Default")
      (node (ref "U1") (pin "53") (pinfunction "P2[10]/~{EINT}0/NMI_53") (pintype "bidirectional"))
    )
    (net (code "110") (name "unconnected-(U1A-P2[11]{slash}~{EINT}1{slash}I2STX_CLK-Pad52)") (class "Default")
      (node (ref "U1") (pin "52") (pinfunction "P2[11]/~{EINT}1/I2STX_CLK_52") (pintype "bidirectional"))
    )
    (net (code "111") (name "unconnected-(U1A-P2[12]{slash}~{EINT}2{slash}I2STX_WS-Pad51)") (class "Default")
      (node (ref "U1") (pin "51") (pinfunction "P2[12]/~{EINT}2/I2STX_WS_51") (pintype "bidirectional"))
    )
    (net (code "112") (name "unconnected-(U1A-P2[13]{slash}~{EINT}3{slash}I2STX_SDA-Pad50)") (class "Default")
      (node (ref "U1") (pin "50") (pinfunction "P2[13]/~{EINT}3/I2STX_SDA_50") (pintype "bidirectional"))
    )
    (net (code "113") (name "unconnected-(U1A-P4[28]{slash}RX_MCLK{slash}MAT2[0]{slash}TXD3-Pad82)") (class "Default")
      (node (ref "U1") (pin "82") (pinfunction "P4[28]/RX_MCLK/MAT2[0]/TXD3_82") (pintype "bidirectional"))
    )
    (net (code "114") (name "unconnected-(U1A-P4[29]{slash}TX_MCLK{slash}MAT2[1]{slash}RXD3-Pad85)") (class "Default")
      (node (ref "U1") (pin "85") (pinfunction "P4[29]/TX_MCLK/MAT2[1]/RXD3_85") (pintype "bidirectional"))
    )
    (net (code "115") (name "unconnected-(U1D-NC-Pad13)") (class "Default")
      (node (ref "U1") (pin "13") (pinfunction "NC_13") (pintype "power_in"))
    )
    (net (code "116") (name "unconnected-(U2-R1IN-Pad13)") (class "Default")
      (node (ref "U2") (pin "13") (pinfunction "R1IN_13") (pintype "passive"))
    )
    (net (code "117") (name "unconnected-(U2-R1OUT-Pad12)") (class "Default")
      (node (ref "U2") (pin "12") (pinfunction "R1OUT_12") (pintype "passive"))
    )
    (net (code "118") (name "unconnected-(U2-T1IN-Pad11)") (class "Default")
      (node (ref "U2") (pin "11") (pinfunction "T1IN_11") (pintype "passive"))
    )
    (net (code "119") (name "unconnected-(U2-T1OUT-Pad14)") (class "Default")
      (node (ref "U2") (pin "14") (pinfunction "T1OUT_14") (pintype "passive"))
    )
  )
)
